# Power.net
KiCad netlist of a schematic drawn in Altium Designer
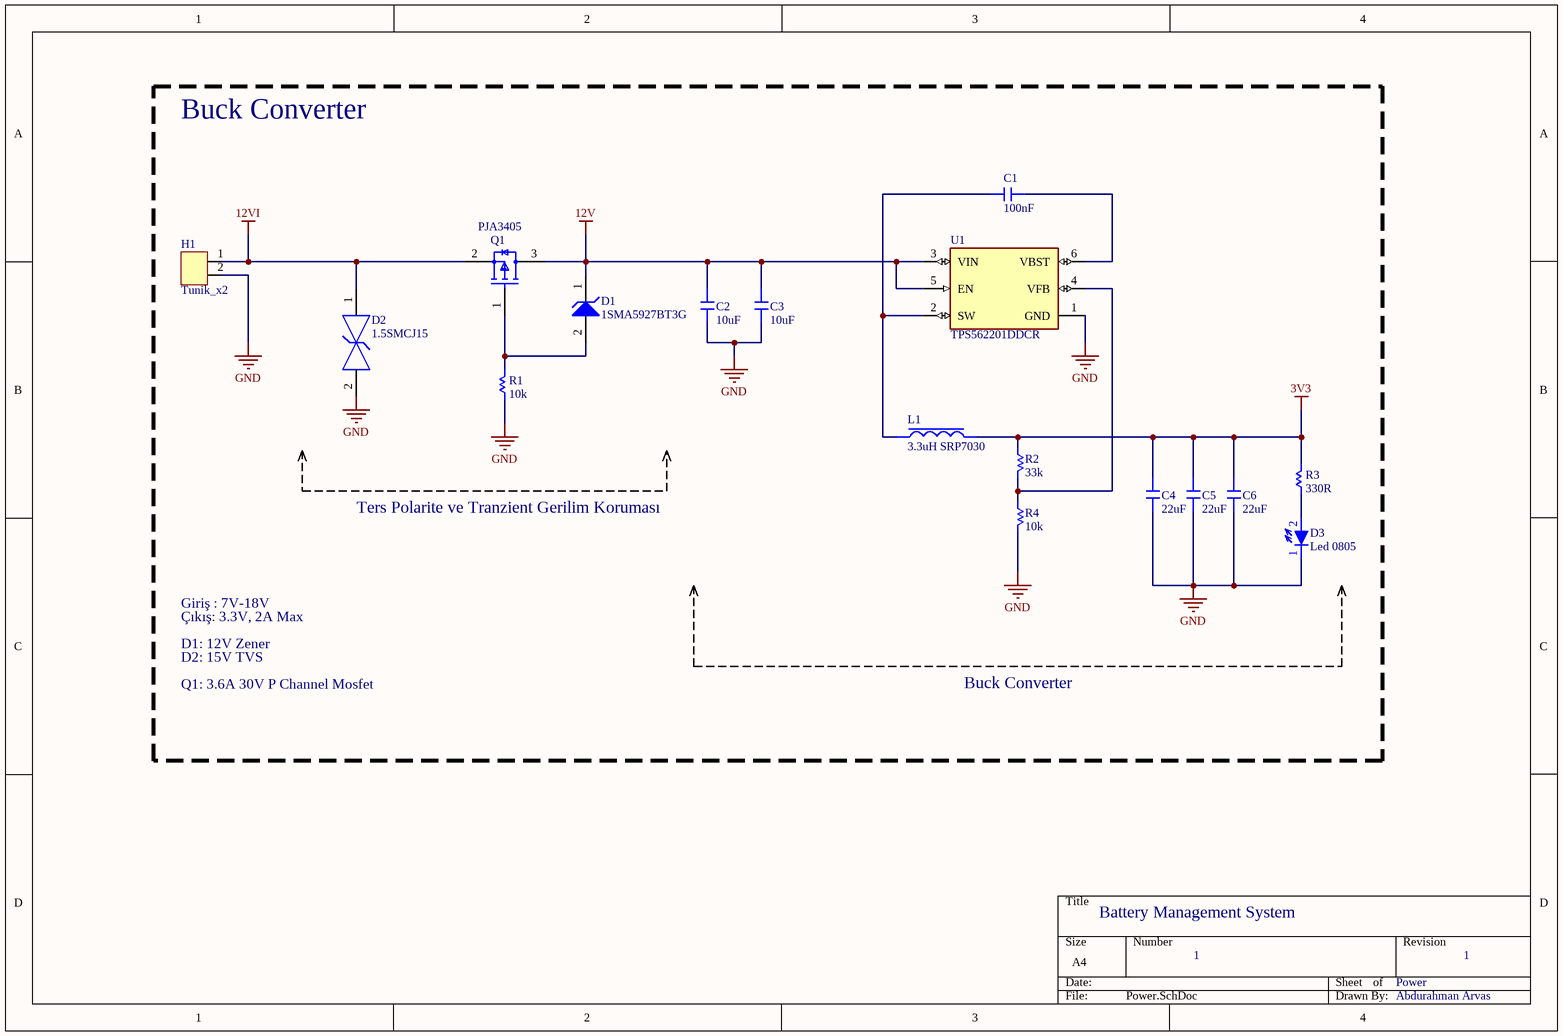
[diagram p0: Power.SchDoc]

(export (version "E")
  (design (tool "Eeschema 10.0.6"))
  (components
    (comp (ref "C1")
      (value "100nF")
      (footprint "C0805")
      (libsource (lib "Arvas_AltiumSCH") (part "SMD_Capacitor"))
    )
    (comp (ref "C2")
      (value "10uF")
      (footprint "C0805")
      (libsource (lib "Arvas_AltiumSCH") (part "SMD_Capacitor"))
    )
    (comp (ref "C3")
      (value "10uF")
      (footprint "C0805")
      (libsource (lib "Arvas_AltiumSCH") (part "SMD_Capacitor"))
    )
    (comp (ref "C4")
      (value "22uF")
      (footprint "C0805")
      (libsource (lib "Arvas_AltiumSCH") (part "SMD_Capacitor"))
    )
    (comp (ref "C5")
      (value "22uF")
      (footprint "C0805")
      (libsource (lib "Arvas_AltiumSCH") (part "SMD_Capacitor"))
    )
    (comp (ref "C6")
      (value "22uF")
      (footprint "C0805")
      (libsource (lib "Arvas_AltiumSCH") (part "SMD_Capacitor"))
    )
    (comp (ref "D1")
      (value "1SMA5927BT3G")
      (footprint "ONSC-SMA-2-403D-02_F_V")
      (description "1.5 W Zener Voltage Regulator, 2-Pin SMA, Pb-Free, Tape and Reel")
      (fields (field (name "MANUFACTURER") "On Semiconductor"))
      (libsource (lib "Altium Content Vault") (part "ONSC-K1A2-2"))
    )
    (comp (ref "D2")
      (value "1.5SMCJ15")
      (footprint "FP-SMC-MFG")
      (description "TVS DIODE 12V 19.9V SMC")
      (fields
        (field (name "MANUFACTURER") "STMicroelectronics")
        (field (name "MANUFACTURER PART NUMBER") "SMC30J12CA")
      )
      (libsource (lib "Altium Content Vault") (part "89c663e49c8877d2c9d183c2997548d"))
    )
    (comp (ref "D3")
      (value "Led 0805")
      (footprint "LED_0805")
      (description "Light Emitting Diode with 0805 Footprint.")
      (libsource (lib "Arvas_AltiumSCH") (part "Led 0805"))
    )
    (comp (ref "H1")
      (value "Tunik_x2")
      (footprint "2li_Tunik")
      (libsource (lib "UET_Lib") (part "2Li_Tunik"))
    )
    (comp (ref "L1")
      (value "3.3uH SRP7030")
      (footprint "Fıxed_Inductor_7.3x7x3")
      (description "Fixed Inductor")
      (libsource (lib "Arvas_AltiumSCH") (part "Fixed_Inductor"))
    )
    (comp (ref "Q1")
      (value "PJA3405")
      (footprint "FP-SOT23-MFG")
      (description "MOSFET P-CH 60V 0.9A SOT23-3")
      (libsource (lib "Altium Content Vault") (part "20f89b0800c15761963a6bd716c5ed7"))
    )
    (comp (ref "R1")
      (value "10k")
      (footprint "R0805")
      (description "SMD Chip Resistor")
      (libsource (lib "Arvas_AltiumSCH") (part "SMD Resistor"))
    )
    (comp (ref "R2")
      (value "33k")
      (footprint "R0805")
      (description "SMD Chip Resistor")
      (libsource (lib "Arvas_AltiumSCH") (part "SMD Resistor"))
    )
    (comp (ref "R3")
      (value "330R")
      (footprint "R0805")
      (description "SMD Chip Resistor")
      (libsource (lib "Arvas_AltiumSCH") (part "SMD Resistor"))
    )
    (comp (ref "R4")
      (value "10k")
      (footprint "R0805")
      (description "SMD Chip Resistor")
      (libsource (lib "Arvas_AltiumSCH") (part "SMD Resistor"))
    )
    (comp (ref "U1")
      (value "TPS562201DDCR")
      (footprint "FP-DDC0006A-IPC_A")
      (description "IC REG BUCK ADJ 2A TSOT23-6")
      (libsource (lib "Altium Content Vault") (part "957e164956730ea4bf6293280af19fc"))
    )
  )
  (nets
    (net (code "1") (name "3V3") (class "Default")
      (node (ref "C4") (pin "2") (pinfunction "2_2") (pintype "passive"))
      (node (ref "C5") (pin "2") (pinfunction "2_2") (pintype "passive"))
      (node (ref "C6") (pin "2") (pinfunction "2_2") (pintype "passive"))
      (node (ref "L1") (pin "2") (pinfunction "2_2") (pintype "passive"))
      (node (ref "R2") (pin "1") (pinfunction "1_1") (pintype "passive"))
      (node (ref "R3") (pin "2") (pinfunction "2_2") (pintype "passive"))
    )
    (net (code "2") (name "12V") (class "Default")
      (node (ref "C2") (pin "2") (pinfunction "2_2") (pintype "passive"))
      (node (ref "C3") (pin "2") (pinfunction "2_2") (pintype "passive"))
      (node (ref "D1") (pin "1") (pinfunction "K_1") (pintype "passive"))
      (node (ref "Q1") (pin "3") (pinfunction "D_3") (pintype "passive"))
      (node (ref "U1") (pin "3") (pinfunction "VIN_3") (pintype "bidirectional"))
      (node (ref "U1") (pin "5") (pinfunction "EN_5") (pintype "input"))
    )
    (net (code "3") (name "12VI") (class "Default")
      (node (ref "D2") (pin "1") (pinfunction "1_1") (pintype "passive"))
      (node (ref "H1") (pin "1") (pinfunction "1_1") (pintype "passive"))
      (node (ref "Q1") (pin "2") (pinfunction "S_2") (pintype "passive"))
    )
    (net (code "4") (name "GND") (class "Default")
      (node (ref "C2") (pin "1") (pinfunction "1_1") (pintype "passive"))
      (node (ref "C3") (pin "1") (pinfunction "1_1") (pintype "passive"))
      (node (ref "C4") (pin "1") (pinfunction "1_1") (pintype "passive"))
      (node (ref "C5") (pin "1") (pinfunction "1_1") (pintype "passive"))
      (node (ref "C6") (pin "1") (pinfunction "1_1") (pintype "passive"))
      (node (ref "D2") (pin "2") (pinfunction "2_2") (pintype "passive"))
      (node (ref "D3") (pin "1") (pinfunction "Cathode_1") (pintype "passive"))
      (node (ref "H1") (pin "2") (pinfunction "2_2") (pintype "passive"))
      (node (ref "R1") (pin "1") (pinfunction "1_1") (pintype "passive"))
      (node (ref "R4") (pin "2") (pinfunction "2_2") (pintype "passive"))
      (node (ref "U1") (pin "1") (pinfunction "GND_1") (pintype "power_in"))
    )
    (net (code "5") (name "Net-(D1-A)") (class "Default")
      (node (ref "D1") (pin "2") (pinfunction "A_2") (pintype "passive"))
      (node (ref "Q1") (pin "1") (pinfunction "G_1") (pintype "passive"))
      (node (ref "R1") (pin "2") (pinfunction "2_2") (pintype "passive"))
    )
    (net (code "6") (name "Net-(D3-Anode)") (class "Default")
      (node (ref "D3") (pin "2") (pinfunction "Anode_2") (pintype "passive"))
      (node (ref "R3") (pin "1") (pinfunction "1_1") (pintype "passive"))
    )
    (net (code "7") (name "Net-(U1-SW)") (class "Default")
      (node (ref "C1") (pin "2") (pinfunction "2_2") (pintype "passive"))
      (node (ref "L1") (pin "1") (pinfunction "1_1") (pintype "passive"))
      (node (ref "U1") (pin "2") (pinfunction "SW_2") (pintype "bidirectional"))
    )
    (net (code "8") (name "Net-(U1-VBST)") (class "Default")
      (node (ref "C1") (pin "1") (pinfunction "1_1") (pintype "passive"))
      (node (ref "U1") (pin "6") (pinfunction "VBST_6") (pintype "bidirectional"))
    )
    (net (code "9") (name "Net-(U1-VFB)") (class "Default")
      (node (ref "R2") (pin "2") (pinfunction "2_2") (pintype "passive"))
      (node (ref "R4") (pin "1") (pinfunction "1_1") (pintype "passive"))
      (node (ref "U1") (pin "4") (pinfunction "VFB_4") (pintype "bidirectional"))
    )
  )
)
